# board.net
KiCad netlist of a schematic drawn in EAGLE
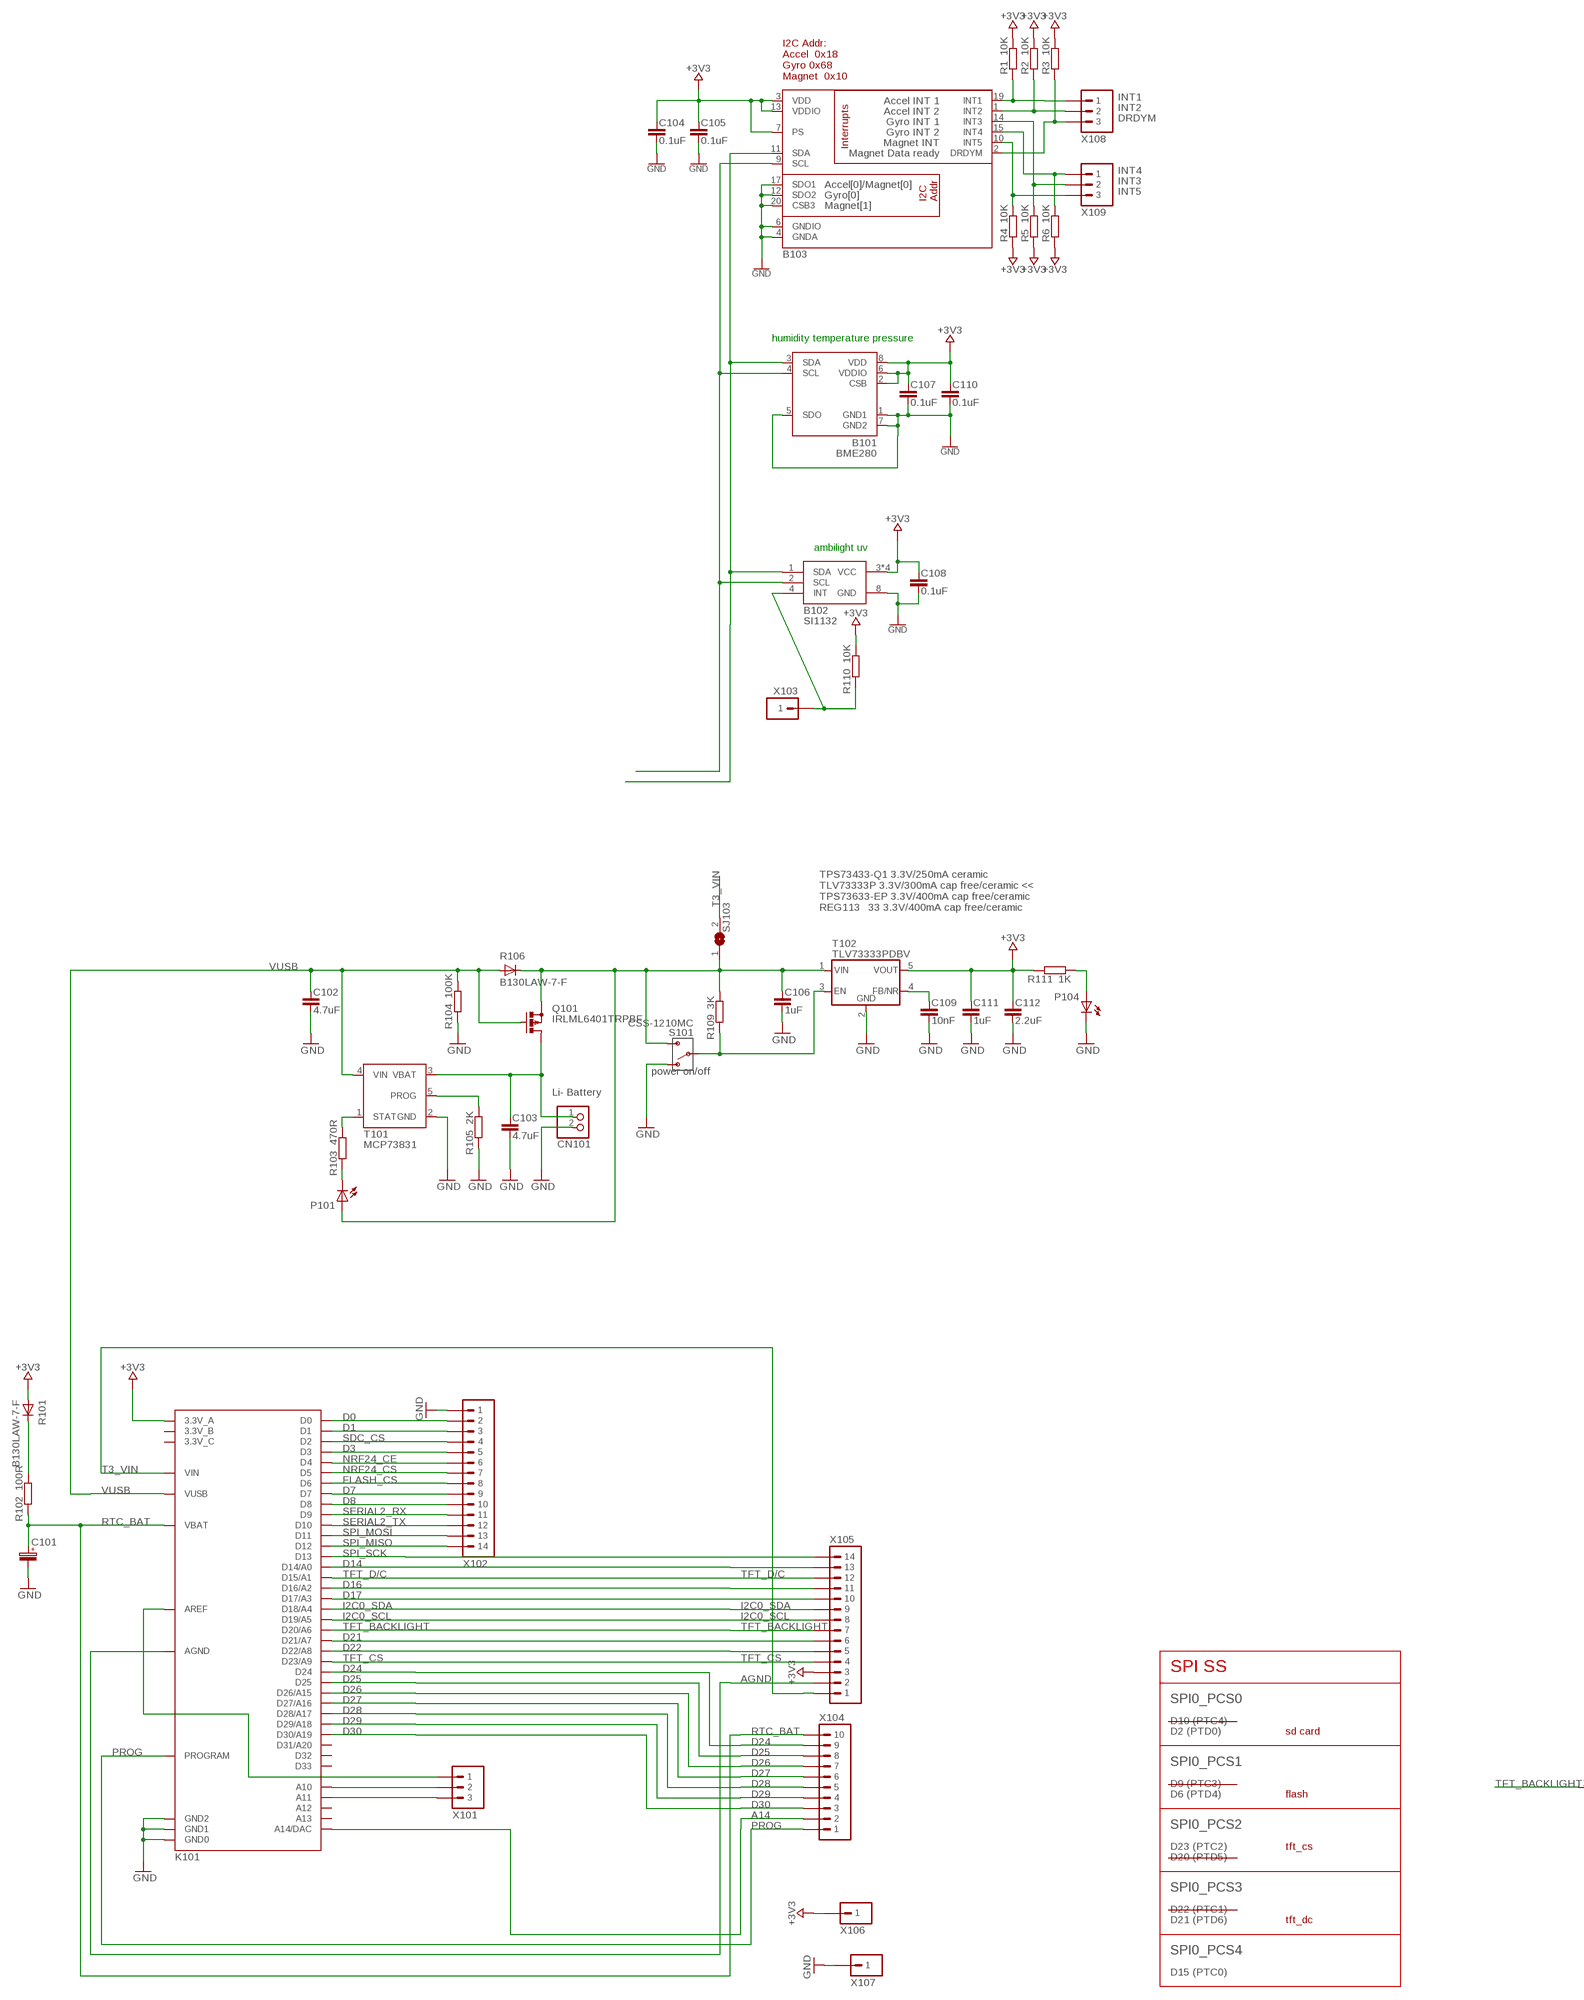
[diagram p0: schematic, sheet 1, part 1 of 2]
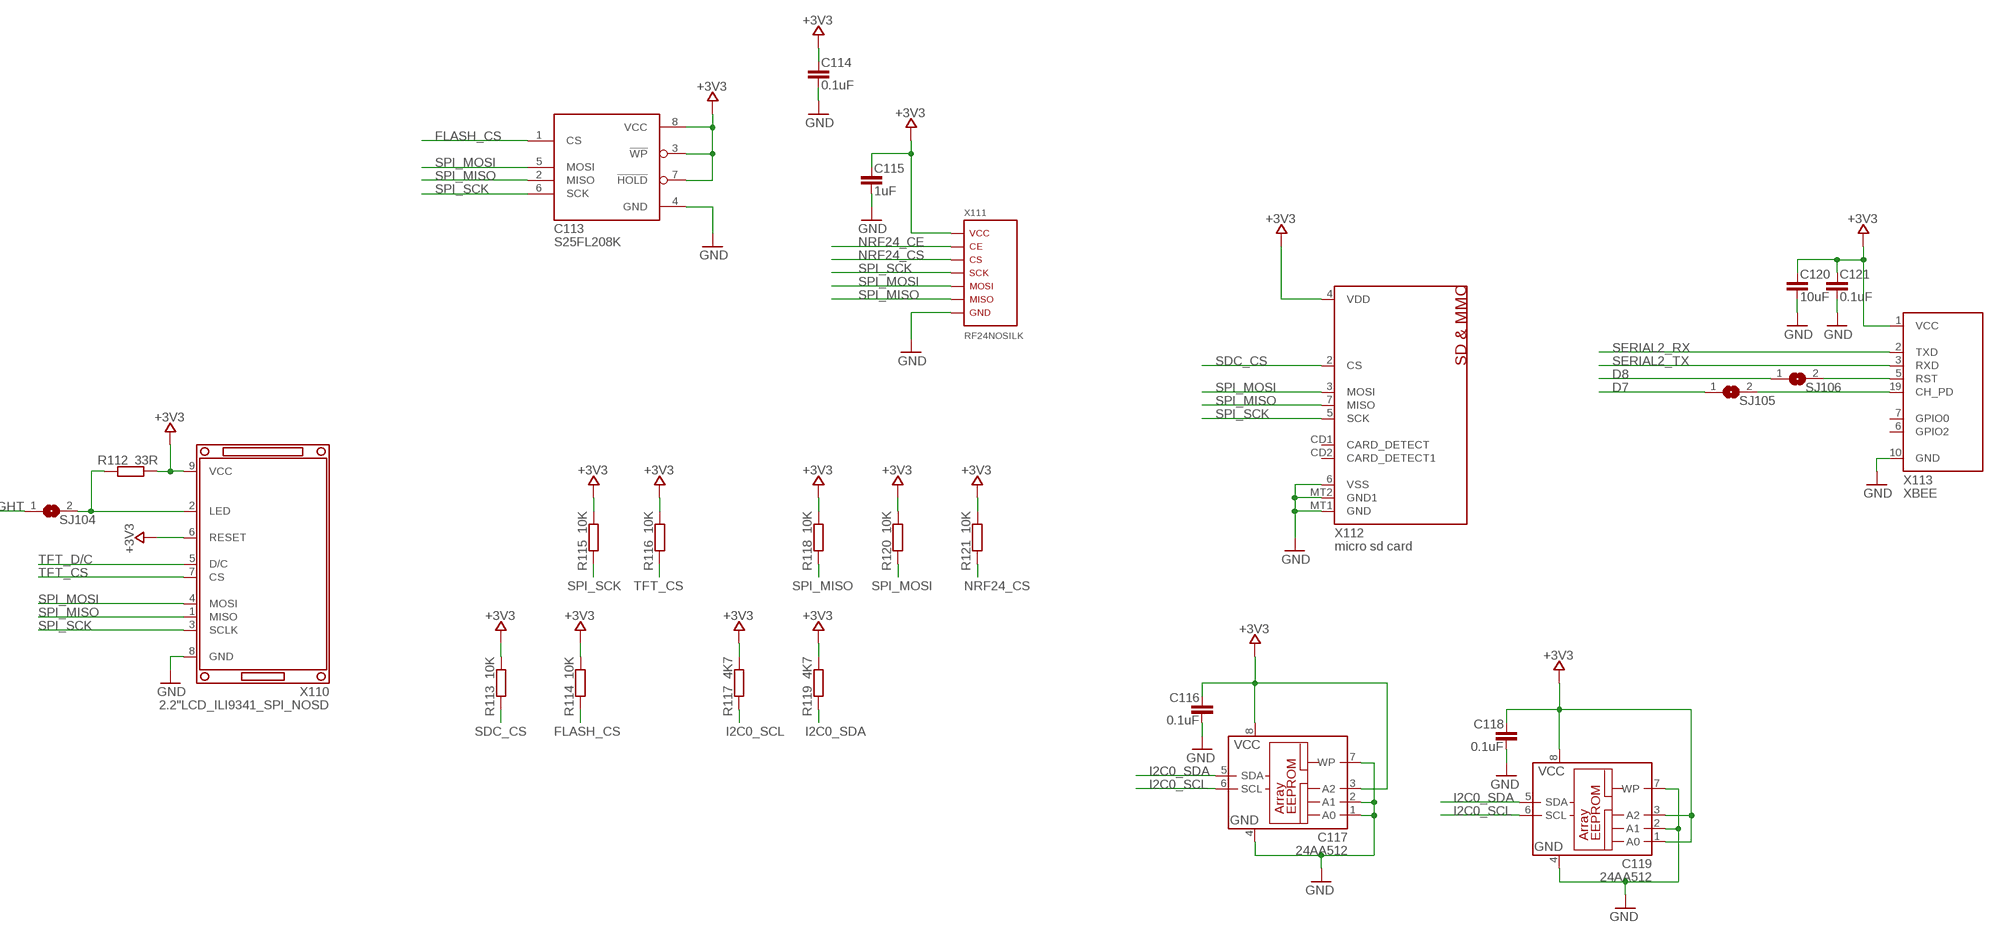
[diagram p1: schematic, sheet 1, part 2 of 2]

(export (version "E")
  (design (tool "Eeschema 10.0.6"))
  (components
    (comp (ref "B101")
      (value "BME280")
      (footprint "eagle-import:BOSCH_8LGA_0.35X0.35")
      (libsource (lib "eagle-import") (part "BME280_I2CLGA8"))
    )
    (comp (ref "B102")
      (value "SI1132")
      (footprint "eagle-import:SILABS_QFN-10_(ONLY_8PAD)")
      (libsource (lib "eagle-import") (part "SI1132QFN10"))
    )
    (comp (ref "B103")
      (value "BMX055")
      (footprint "eagle-import:BMX055_LGA20")
      (libsource (lib "eagle-import") (part "BMX055"))
    )
    (comp (ref "C101")
      (value "CAPACITOR_POLCPH3225A")
      (footprint "eagle-import:CPH3225A")
      (libsource (lib "eagle-import") (part "CAPACITOR_POLCPH3225A"))
    )
    (comp (ref "C102")
      (value "4.7uF")
      (footprint "eagle-import:SMT_M2012(0805)_G1")
      (fields (field (name "MF") "AVX") (field (name "MPN") "0805ZD475KAT2A"))
      (libsource (lib "eagle-import") (part "CAPACITORM2012(0805)_G1"))
    )
    (comp (ref "C103")
      (value "4.7uF")
      (footprint "eagle-import:SMT_M2012(0805)_G1")
      (fields (field (name "MF") "AVX") (field (name "MPN") "0805ZD475KAT2A"))
      (libsource (lib "eagle-import") (part "CAPACITORM2012(0805)_G1"))
    )
    (comp (ref "C104")
      (value "0.1uF")
      (footprint "eagle-import:SMT_M1608(0603)_G1")
      (fields (field (name "MF") "AVX") (field (name "MPN") "0603YC104K4Z2A"))
      (libsource (lib "eagle-import") (part "CAPACITORM1608(0603)_G1"))
    )
    (comp (ref "C105")
      (value "0.1uF")
      (footprint "eagle-import:SMT_M1608(0603)_G1")
      (fields (field (name "MF") "AVX") (field (name "MPN") "0603YC104K4Z2A"))
      (libsource (lib "eagle-import") (part "CAPACITORM1608(0603)_G1"))
    )
    (comp (ref "C106")
      (value "1uF")
      (footprint "eagle-import:SMT_M1608(0603)_G1")
      (fields (field (name "MF") "AVX") (field (name "MPN") "0603ZD105KAT2A"))
      (libsource (lib "eagle-import") (part "CAPACITORM1608(0603)_G1"))
    )
    (comp (ref "C107")
      (value "0.1uF")
      (footprint "eagle-import:SMT_M1608(0603)_G1")
      (fields (field (name "MF") "AVX") (field (name "MPN") "0603YC104K4Z2A"))
      (libsource (lib "eagle-import") (part "CAPACITORM1608(0603)_G1"))
    )
    (comp (ref "C108")
      (value "0.1uF")
      (footprint "eagle-import:SMT_M1608(0603)_G1")
      (fields (field (name "MF") "AVX") (field (name "MPN") "0603YC104K4Z2A"))
      (libsource (lib "eagle-import") (part "CAPACITORM1608(0603)_G1"))
    )
    (comp (ref "C109")
      (value "10nF")
      (footprint "eagle-import:SMT_M1608(0603)_G1")
      (fields (field (name "MF") "MULTICOMP") (field (name "MPN") "MC0603B103K500CT"))
      (libsource (lib "eagle-import") (part "CAPACITORM1608(0603)_G1"))
    )
    (comp (ref "C110")
      (value "0.1uF")
      (footprint "eagle-import:SMT_M1608(0603)_G1")
      (fields (field (name "MF") "AVX") (field (name "MPN") "0603YC104K4Z2A"))
      (libsource (lib "eagle-import") (part "CAPACITORM1608(0603)_G1"))
    )
    (comp (ref "C111")
      (value "1uF")
      (footprint "eagle-import:SMT_M1608(0603)_G1")
      (fields (field (name "MF") "AVX") (field (name "MPN") "0603ZD105KAT2A"))
      (libsource (lib "eagle-import") (part "CAPACITORM1608(0603)_G1"))
    )
    (comp (ref "C112")
      (value "2.2uF")
      (footprint "eagle-import:SMT_M2012(0805)_G1")
      (fields (field (name "MF") "KEMET") (field (name "MPN") "C1206C226K9PACTU"))
      (libsource (lib "eagle-import") (part "CAPACITORM2012(0805)_G1"))
    )
    (comp (ref "C113")
      (value "S25FL208K")
      (footprint "eagle-import:SOIC-8")
      (fields (field (name "MF") "SPANSION") (field (name "MPN") "S25FL208K0RMFI041"))
      (libsource (lib "eagle-import") (part "SPI_FLASH-X25XXSOIC_150MIL_2"))
    )
    (comp (ref "C114")
      (value "0.1uF")
      (footprint "eagle-import:SMT_M1608(0603)_G1")
      (fields (field (name "MF") "AVX") (field (name "MPN") "0603YC104K4Z2A"))
      (libsource (lib "eagle-import") (part "CAPACITORM1608(0603)_G1"))
    )
    (comp (ref "C115")
      (value "1uF")
      (footprint "eagle-import:SMT_M1608(0603)_G1")
      (fields (field (name "MF") "AVX") (field (name "MPN") "0603ZD105KAT2A"))
      (libsource (lib "eagle-import") (part "CAPACITORM1608(0603)_G1"))
    )
    (comp (ref "C116")
      (value "0.1uF")
      (footprint "eagle-import:SMT_M1608(0603)_G1")
      (fields (field (name "MF") "AVX") (field (name "MPN") "0603YC104K4Z2A"))
      (libsource (lib "eagle-import") (part "CAPACITORM1608(0603)_G1"))
    )
    (comp (ref "C117")
      (value "24AA512")
      (footprint "eagle-import:SOIC-8")
      (fields (field (name "MF") "MICROCHIP") (field (name "MPN") "24AA512-I/SM"))
      (libsource (lib "eagle-import") (part "EEPROM24AAXXXSN"))
    )
    (comp (ref "C118")
      (value "0.1uF")
      (footprint "eagle-import:SMT_M1608(0603)_G1")
      (fields (field (name "MF") "AVX") (field (name "MPN") "0603YC104K4Z2A"))
      (libsource (lib "eagle-import") (part "CAPACITORM1608(0603)_G1"))
    )
    (comp (ref "C119")
      (value "24AA512")
      (footprint "eagle-import:SOIC-8")
      (fields (field (name "MF") "MICROCHIP") (field (name "MPN") "24AA512-I/SM"))
      (libsource (lib "eagle-import") (part "EEPROM24AAXXXSN"))
    )
    (comp (ref "C120")
      (value "10uF")
      (footprint "eagle-import:SMT_M2012(0805)_G1")
      (fields (field (name "MF") "MULTICOMP") (field (name "MPN") "MCTT31F106Z100CT"))
      (libsource (lib "eagle-import") (part "CAPACITORM2012(0805)_G1"))
    )
    (comp (ref "C121")
      (value "0.1uF")
      (footprint "eagle-import:SMT_M1608(0603)_G1")
      (fields (field (name "MF") "AVX") (field (name "MPN") "0603YC104K4Z2A"))
      (libsource (lib "eagle-import") (part "CAPACITORM1608(0603)_G1"))
    )
    (comp (ref "CN101")
      (value "JST_2PIN-SMT-RA")
      (footprint "eagle-import:JST-PH-2-SMT-RA")
      (fields
        (field (name "MF") "JST (JAPAN SOLDERLESS TERMINALS)")
        (field (name "MPN") "S2B-PH-SM4-TB(LF)(SN)")
      )
      (libsource (lib "eagle-import") (part "JST_2PIN-SMT-RA"))
    )
    (comp (ref "K101")
      (value "TEENSY3.1_ALLPINSNOSILK")
      (footprint "eagle-import:TEENSY3.1_ALLPINS_NOSILK")
      (libsource (lib "eagle-import") (part "TEENSY3.1_ALLPINSNOSILK"))
    )
    (comp (ref "P101")
      (value "LEDSMT_M1608(0603)_LED_G1")
      (footprint "eagle-import:SMT_M1608(0603)_LED_G1")
      (fields (field (name "MF") "VISHAY SEMICONDUCTOR") (field (name "MPN") "TLMS1100-GS08"))
      (libsource (lib "eagle-import") (part "LEDSMT_M1608(0603)_LED_G1"))
    )
    (comp (ref "P104")
      (value "LEDSMT_M1608(0603)_LED_G1")
      (footprint "eagle-import:SMT_M1608(0603)_LED_G1")
      (fields (field (name "MF") "VISHAY SEMICONDUCTOR") (field (name "MPN") "TLMS1100-GS08"))
      (libsource (lib "eagle-import") (part "LEDSMT_M1608(0603)_LED_G1"))
    )
    (comp (ref "Q101")
      (value "IRLML6401TRPBF")
      (footprint "eagle-import:SOT23-SPEC1")
      (fields (field (name "MF") "INTERNATIONAL RECTIFIER"))
      (libsource (lib "eagle-import") (part "PFETSOT-23_SPEC1"))
    )
    (comp (ref "R1")
      (value "10K")
      (footprint "eagle-import:SMT_M1608(0603)_G1")
      (fields (field (name "MF") "VISHAY DRALORIC") (field (name "MPN") "CRCW060310K0FKEA"))
      (libsource (lib "eagle-import") (part "RESISTORM1608(0603)_G1"))
    )
    (comp (ref "R2")
      (value "10K")
      (footprint "eagle-import:SMT_M1608(0603)_G1")
      (fields (field (name "MF") "VISHAY DRALORIC") (field (name "MPN") "CRCW060310K0FKEA"))
      (libsource (lib "eagle-import") (part "RESISTORM1608(0603)_G1"))
    )
    (comp (ref "R3")
      (value "10K")
      (footprint "eagle-import:SMT_M1608(0603)_G1")
      (fields (field (name "MF") "VISHAY DRALORIC") (field (name "MPN") "CRCW060310K0FKEA"))
      (libsource (lib "eagle-import") (part "RESISTORM1608(0603)_G1"))
    )
    (comp (ref "R4")
      (value "10K")
      (footprint "eagle-import:SMT_M1608(0603)_G1")
      (fields (field (name "MF") "VISHAY DRALORIC") (field (name "MPN") "CRCW060310K0FKEA"))
      (libsource (lib "eagle-import") (part "RESISTORM1608(0603)_G1"))
    )
    (comp (ref "R5")
      (value "10K")
      (footprint "eagle-import:SMT_M1608(0603)_G1")
      (fields (field (name "MF") "VISHAY DRALORIC") (field (name "MPN") "CRCW060310K0FKEA"))
      (libsource (lib "eagle-import") (part "RESISTORM1608(0603)_G1"))
    )
    (comp (ref "R6")
      (value "10K")
      (footprint "eagle-import:SMT_M1608(0603)_G1")
      (fields (field (name "MF") "VISHAY DRALORIC") (field (name "MPN") "CRCW060310K0FKEA"))
      (libsource (lib "eagle-import") (part "RESISTORM1608(0603)_G1"))
    )
    (comp (ref "R101")
      (value "B130LAW-7-F")
      (footprint "eagle-import:SOD123V2")
      (fields (field (name "MF") "DIODES INC."))
      (libsource (lib "eagle-import") (part "DIODESOD123-V2"))
    )
    (comp (ref "R102")
      (value "100R")
      (footprint "eagle-import:SMT_M1608(0603)_G1")
      (fields (field (name "MF") "VISHAY DRALORIC") (field (name "MPN") "CRCW060310K0FKEA"))
      (libsource (lib "eagle-import") (part "RESISTORM1608(0603)_G1"))
    )
    (comp (ref "R103")
      (value "470R")
      (footprint "eagle-import:SMT_M1608(0603)_G1")
      (fields (field (name "MF") "VISHAY DRALORIC") (field (name "MPN") "CRCW0603470RFKEA"))
      (libsource (lib "eagle-import") (part "RESISTORM1608(0603)_G1"))
    )
    (comp (ref "R104")
      (value "100K")
      (footprint "eagle-import:SMT_M1608(0603)_G1")
      (fields (field (name "MF") "VISHAY DRALORIC") (field (name "MPN") "CRCW060310K0FKEA"))
      (libsource (lib "eagle-import") (part "RESISTORM1608(0603)_G1"))
    )
    (comp (ref "R105")
      (value "2K")
      (footprint "eagle-import:SMT_M1608(0603)_G1")
      (fields (field (name "MF") "VISHAY DRALORIC") (field (name "MPN") "CRCW06032K00FKEA"))
      (libsource (lib "eagle-import") (part "RESISTORM1608(0603)_G1"))
    )
    (comp (ref "R106")
      (value "B130LAW-7-F")
      (footprint "eagle-import:SOD123V2")
      (fields (field (name "MF") "DIODES INC."))
      (libsource (lib "eagle-import") (part "DIODESOD123-V2"))
    )
    (comp (ref "R109")
      (value "3K")
      (footprint "eagle-import:SMT_M1608(0603)_G1")
      (fields (field (name "MF") "VISHAY DRALORIC") (field (name "MPN") "CRCW06033K00FKEA"))
      (libsource (lib "eagle-import") (part "RESISTORM1608(0603)_G1"))
    )
    (comp (ref "R110")
      (value "10K")
      (footprint "eagle-import:SMT_M1608(0603)_G1")
      (libsource (lib "eagle-import") (part "RESISTORM1608(0603)_G1"))
    )
    (comp (ref "R111")
      (value "1K")
      (footprint "eagle-import:SMT_M1608(0603)_G1")
      (fields (field (name "MF") "VISHAY DRALORIC") (field (name "MPN") "CRCW0603330RFKEA"))
      (libsource (lib "eagle-import") (part "RESISTORM1608(0603)_G1"))
    )
    (comp (ref "R112")
      (value "33R")
      (footprint "eagle-import:SMT_M1608(0603)_G1")
      (fields (field (name "MF") "VISHAY DRALORIC") (field (name "MPN") "CRCW0805100RFKEA"))
      (libsource (lib "eagle-import") (part "RESISTORM1608(0603)_G1"))
    )
    (comp (ref "R113")
      (value "10K")
      (footprint "eagle-import:SMT_M1608(0603)_G1")
      (fields (field (name "MF") "VISHAY DRALORIC") (field (name "MPN") "CRCW060310K0FKEA"))
      (libsource (lib "eagle-import") (part "RESISTORM1608(0603)_G1"))
    )
    (comp (ref "R114")
      (value "10K")
      (footprint "eagle-import:SMT_M1608(0603)_G1")
      (fields (field (name "MF") "VISHAY DRALORIC") (field (name "MPN") "CRCW060310K0FKEA"))
      (libsource (lib "eagle-import") (part "RESISTORM1608(0603)_G1"))
    )
    (comp (ref "R115")
      (value "10K")
      (footprint "eagle-import:SMT_M1608(0603)_G1")
      (fields (field (name "MF") "VISHAY DRALORIC") (field (name "MPN") "CRCW060310K0FKEA"))
      (libsource (lib "eagle-import") (part "RESISTORM1608(0603)_G1"))
    )
    (comp (ref "R116")
      (value "10K")
      (footprint "eagle-import:SMT_M1608(0603)_G1")
      (fields (field (name "MF") "VISHAY DRALORIC") (field (name "MPN") "CRCW060310K0FKEA"))
      (libsource (lib "eagle-import") (part "RESISTORM1608(0603)_G1"))
    )
    (comp (ref "R117")
      (value "4K7")
      (footprint "eagle-import:SMT_M1608(0603)_G1")
      (fields (field (name "MF") "VISHAY DRALORIC") (field (name "MPN") "CRCW06034K70FKEA"))
      (libsource (lib "eagle-import") (part "RESISTORM1608(0603)_G1"))
    )
    (comp (ref "R118")
      (value "10K")
      (footprint "eagle-import:SMT_M1608(0603)_G1")
      (fields (field (name "MF") "VISHAY DRALORIC") (field (name "MPN") "CRCW060310K0FKEA"))
      (libsource (lib "eagle-import") (part "RESISTORM1608(0603)_G1"))
    )
    (comp (ref "R119")
      (value "4K7")
      (footprint "eagle-import:SMT_M1608(0603)_G1")
      (fields (field (name "MF") "VISHAY DRALORIC") (field (name "MPN") "CRCW06034K70FKEA"))
      (libsource (lib "eagle-import") (part "RESISTORM1608(0603)_G1"))
    )
    (comp (ref "R120")
      (value "10K")
      (footprint "eagle-import:SMT_M1608(0603)_G1")
      (fields (field (name "MF") "VISHAY DRALORIC") (field (name "MPN") "CRCW060310K0FKEA"))
      (libsource (lib "eagle-import") (part "RESISTORM1608(0603)_G1"))
    )
    (comp (ref "R121")
      (value "10K")
      (footprint "eagle-import:SMT_M1608(0603)_G1")
      (fields (field (name "MF") "VISHAY DRALORIC") (field (name "MPN") "CRCW060310K0FKEA"))
      (libsource (lib "eagle-import") (part "RESISTORM1608(0603)_G1"))
    )
    (comp (ref "S101")
      (value "CSS-1210MC")
      (footprint "eagle-import:CSS-1210(M)C")
      (libsource (lib "eagle-import") (part "SLIDE_SWITCH_2WAYCSS-1210(M)C"))
    )
    (comp (ref "SJ103")
      (value "n/a")
      (footprint "eagle-import:SMT_M1608(0603)_G1")
      (libsource (lib "eagle-import") (part "JUMPER_2WRESISTOR0603"))
    )
    (comp (ref "SJ104")
      (value "n/a")
      (footprint "eagle-import:SMT_M1608(0603)_G1")
      (libsource (lib "eagle-import") (part "JUMPER_2WRESISTOR0603"))
    )
    (comp (ref "SJ105")
      (value "0R")
      (footprint "eagle-import:SMT_M1608(0603)_G1")
      (libsource (lib "eagle-import") (part "JUMPER_2WRESISTOR0603"))
    )
    (comp (ref "SJ106")
      (value "0R")
      (footprint "eagle-import:SMT_M1608(0603)_G1")
      (libsource (lib "eagle-import") (part "JUMPER_2WRESISTOR0603"))
    )
    (comp (ref "T101")
      (value "MCP73831")
      (footprint "eagle-import:SOT23-5_MICROCHIP")
      (fields (field (name "MF") "MICROCHIP") (field (name "MPN") "MCP73831T-2ATI/OT"))
      (libsource (lib "eagle-import") (part "MCP73831XXXX/OT_(SOT-23)"))
    )
    (comp (ref "T102")
      (value "TLV73333PDBV")
      (footprint "eagle-import:R-PDSO-G5")
      (fields (field (name "MF") "TEXAS INSTRUMENTS") (field (name "MPN") "TLV73333PDBVT"))
      (libsource (lib "eagle-import") (part "TPS736XXDBV_1"))
    )
    (comp (ref "X101")
      (value "3P1/MIN_SILK2")
      (footprint "eagle-import:HEADER_1X3_1_MIN_SILK2")
      (libsource (lib "eagle-import") (part "3P1/MIN_SILK2"))
    )
    (comp (ref "X102")
      (value "14P1/MIN_SILK2")
      (footprint "eagle-import:HEADER_1X14_1_MIN_SILK2")
      (libsource (lib "eagle-import") (part "14P1/MIN_SILK2"))
    )
    (comp (ref "X103")
      (value "1P1/MIN_SILK2")
      (footprint "eagle-import:HEADER_1X1_1_MIN_SILK2")
      (libsource (lib "eagle-import") (part "1P1/MIN_SILK2"))
    )
    (comp (ref "X104")
      (value "10P1X10P_1/MIN_SILK2")
      (footprint "eagle-import:HEADER_1X10_1_MIN_SILK2")
      (libsource (lib "eagle-import") (part "10P1X10P_1/MIN_SILK2"))
    )
    (comp (ref "X105")
      (value "14P1/MIN_SILK2")
      (footprint "eagle-import:HEADER_1X14_1_MIN_SILK2")
      (libsource (lib "eagle-import") (part "14P1/MIN_SILK2"))
    )
    (comp (ref "X106")
      (value "1P1/MIN_SILK2")
      (footprint "eagle-import:HEADER_1X1_1_MIN_SILK2")
      (libsource (lib "eagle-import") (part "1P1/MIN_SILK2"))
    )
    (comp (ref "X107")
      (value "1P1/MIN_SILK2")
      (footprint "eagle-import:HEADER_1X1_1_MIN_SILK2")
      (libsource (lib "eagle-import") (part "1P1/MIN_SILK2"))
    )
    (comp (ref "X108")
      (value "3P1/MIN_SILK2")
      (footprint "eagle-import:HEADER_1X3_1_MIN_SILK2")
      (libsource (lib "eagle-import") (part "3P1/MIN_SILK2"))
    )
    (comp (ref "X109")
      (value "3P1/MIN_SILK2")
      (footprint "eagle-import:HEADER_1X3_1_MIN_SILK2")
      (libsource (lib "eagle-import") (part "3P1/MIN_SILK2"))
    )
    (comp (ref "X110")
      (value "2.2\"LCD_ILI9341_SPI_NOSD")
      (footprint "eagle-import:2.2_TFT1")
      (libsource (lib "eagle-import") (part "2.2{dblquote}LCD_ILI9341_SPI_NOSD"))
    )
    (comp (ref "X111")
      (value "RF24NOSILK")
      (footprint "eagle-import:RF24_NOSILK")
      (libsource (lib "eagle-import") (part "RF24NOSILK"))
    )
    (comp (ref "X112")
      (value "micro sd card")
      (footprint "eagle-import:MICROSD")
      (fields (field (name "MF") "GLOBAL CONNECTOR TECHNOLOGY") (field (name "MPN") "MEM2051-00-195-00-A."))
      (libsource (lib "eagle-import") (part "MICROSD"))
    )
    (comp (ref "X113")
      (value "XBEE")
      (footprint "eagle-import:ESP_BEE_PTH_VCC_GND_RX_TX_PD_RST_IO0_IO2")
      (libsource (lib "eagle-import") (part "EXP-BEE-SMALLPTH"))
    )
  )
  (nets
    (net (code "1") (name "+3V3") (class "Default")
      (node (ref "B101") (pin "2") (pinfunction "CSB_2") (pintype "bidirectional"))
      (node (ref "B101") (pin "6") (pinfunction "VDDIO_6") (pintype "bidirectional"))
      (node (ref "B101") (pin "8") (pinfunction "VDD_8") (pintype "bidirectional"))
      (node (ref "B102") (pin "3") (pinfunction "VCC_3") (pintype "bidirectional"))
      (node (ref "B102") (pin "6") (pinfunction "VCC_6") (pintype "bidirectional"))
      (node (ref "B102") (pin "7") (pinfunction "VCC_7") (pintype "bidirectional"))
      (node (ref "B102") (pin "9") (pinfunction "VCC_9") (pintype "bidirectional"))
      (node (ref "B103") (pin "13") (pinfunction "VDDIO_13") (pintype "bidirectional"))
      (node (ref "B103") (pin "3") (pinfunction "VDD_3") (pintype "bidirectional"))
      (node (ref "B103") (pin "7") (pinfunction "PS_7") (pintype "bidirectional"))
      (node (ref "C104") (pin "1") (pinfunction "1_1") (pintype "passive"))
      (node (ref "C105") (pin "1") (pinfunction "1_1") (pintype "passive"))
      (node (ref "C107") (pin "1") (pinfunction "1_1") (pintype "passive"))
      (node (ref "C108") (pin "1") (pinfunction "1_1") (pintype "passive"))
      (node (ref "C110") (pin "1") (pinfunction "1_1") (pintype "passive"))
      (node (ref "C111") (pin "1") (pinfunction "1_1") (pintype "passive"))
      (node (ref "C112") (pin "1") (pinfunction "1_1") (pintype "passive"))
      (node (ref "C113") (pin "3") (pinfunction "~{WP}_3") (pintype "bidirectional"))
      (node (ref "C113") (pin "7") (pinfunction "~{HOLD}_7") (pintype "bidirectional"))
      (node (ref "C113") (pin "8") (pinfunction "VCC_8") (pintype "bidirectional"))
      (node (ref "C114") (pin "1") (pinfunction "1_1") (pintype "passive"))
      (node (ref "C115") (pin "1") (pinfunction "1_1") (pintype "passive"))
      (node (ref "C116") (pin "1") (pinfunction "1_1") (pintype "passive"))
      (node (ref "C117") (pin "3") (pinfunction "A2_3") (pintype "input"))
      (node (ref "C117") (pin "8") (pinfunction "VCC_8") (pintype "power_in"))
      (node (ref "C118") (pin "1") (pinfunction "1_1") (pintype "passive"))
      (node (ref "C119") (pin "1") (pinfunction "A0_1") (pintype "input"))
      (node (ref "C119") (pin "3") (pinfunction "A2_3") (pintype "input"))
      (node (ref "C119") (pin "8") (pinfunction "VCC_8") (pintype "power_in"))
      (node (ref "C120") (pin "1") (pinfunction "1_1") (pintype "passive"))
      (node (ref "C121") (pin "1") (pinfunction "1_1") (pintype "passive"))
      (node (ref "K101") (pin "3V3_A") (pinfunction "3.3V_A_3V3_A") (pintype "power_in"))
      (node (ref "R1") (pin "2") (pinfunction "2_2") (pintype "passive"))
      (node (ref "R101") (pin "A") (pinfunction "A_A") (pintype "passive"))
      (node (ref "R110") (pin "2") (pinfunction "2_2") (pintype "passive"))
      (node (ref "R111") (pin "1") (pinfunction "1_1") (pintype "passive"))
      (node (ref "R112") (pin "2") (pinfunction "2_2") (pintype "passive"))
      (node (ref "R113") (pin "2") (pinfunction "2_2") (pintype "passive"))
      (node (ref "R114") (pin "2") (pinfunction "2_2") (pintype "passive"))
      (node (ref "R115") (pin "2") (pinfunction "2_2") (pintype "passive"))
      (node (ref "R116") (pin "2") (pinfunction "2_2") (pintype "passive"))
      (node (ref "R117") (pin "2") (pinfunction "2_2") (pintype "passive"))
      (node (ref "R118") (pin "2") (pinfunction "2_2") (pintype "passive"))
      (node (ref "R119") (pin "2") (pinfunction "2_2") (pintype "passive"))
      (node (ref "R120") (pin "2") (pinfunction "2_2") (pintype "passive"))
      (node (ref "R121") (pin "2") (pinfunction "2_2") (pintype "passive"))
      (node (ref "R2") (pin "2") (pinfunction "2_2") (pintype "passive"))
      (node (ref "R3") (pin "2") (pinfunction "2_2") (pintype "passive"))
      (node (ref "R4") (pin "1") (pinfunction "1_1") (pintype "passive"))
      (node (ref "R5") (pin "1") (pinfunction "1_1") (pintype "passive"))
      (node (ref "R6") (pin "1") (pinfunction "1_1") (pintype "passive"))
      (node (ref "T102") (pin "5") (pinfunction "VOUT_5") (pintype "power_in"))
      (node (ref "X105") (pin "3") (pinfunction "3_3") (pintype "passive"))
      (node (ref "X106") (pin "1") (pinfunction "1_1") (pintype "passive"))
      (node (ref "X110") (pin "6") (pinfunction "RESET_6") (pintype "bidirectional"))
      (node (ref "X110") (pin "9") (pinfunction "VCC_9") (pintype "bidirectional"))
      (node (ref "X111") (pin "VCC") (pinfunction "VCC_VCC") (pintype "power_in"))
      (node (ref "X112") (pin "4") (pinfunction "VDD_4") (pintype "power_in"))
      (node (ref "X113") (pin "1") (pinfunction "VCC_1") (pintype "bidirectional"))
    )
    (net (code "2") (name "/3.3V_B") (class "Default")
      (node (ref "K101") (pin "3V3_B") (pinfunction "3.3V_B_3V3_B") (pintype "power_in"))
    )
    (net (code "3") (name "/3.3V_C") (class "Default")
      (node (ref "K101") (pin "3V3_C") (pinfunction "3.3V_C_3V3_C") (pintype "power_in"))
    )
    (net (code "4") (name "/A14") (class "Default")
      (node (ref "K101") (pin "A14") (pinfunction "A14/DAC_A14") (pintype "input"))
      (node (ref "X104") (pin "2") (pinfunction "2_2") (pintype "passive"))
    )
    (net (code "5") (name "/AGND") (class "Default")
      (node (ref "K101") (pin "AGND") (pinfunction "AGND_AGND") (pintype "bidirectional"))
      (node (ref "X105") (pin "2") (pinfunction "2_2") (pintype "passive"))
    )
    (net (code "6") (name "/D0") (class "Default")
      (node (ref "K101") (pin "D0") (pinfunction "D0_D0") (pintype "bidirectional"))
      (node (ref "X102") (pin "2") (pinfunction "2_2") (pintype "passive"))
    )
    (net (code "7") (name "/D1") (class "Default")
      (node (ref "K101") (pin "D1") (pinfunction "D1_D1") (pintype "bidirectional"))
      (node (ref "X102") (pin "3") (pinfunction "3_3") (pintype "passive"))
    )
    (net (code "8") (name "/D3") (class "Default")
      (node (ref "K101") (pin "D3") (pinfunction "D3_D3") (pintype "bidirectional"))
      (node (ref "X102") (pin "5") (pinfunction "5_5") (pintype "passive"))
    )
    (net (code "9") (name "/D7") (class "Default")
      (node (ref "K101") (pin "D7") (pinfunction "D7_D7") (pintype "bidirectional"))
      (node (ref "SJ105") (pin "1") (pinfunction "1_1") (pintype "passive"))
      (node (ref "X102") (pin "9") (pinfunction "9_9") (pintype "passive"))
    )
    (net (code "10") (name "/D8") (class "Default")
      (node (ref "K101") (pin "D8") (pinfunction "D8_D8") (pintype "bidirectional"))
      (node (ref "SJ106") (pin "1") (pinfunction "1_1") (pintype "passive"))
      (node (ref "X102") (pin "10") (pinfunction "10_10") (pintype "passive"))
    )
    (net (code "11") (name "/D14") (class "Default")
      (node (ref "K101") (pin "A0") (pinfunction "D14/A0_A0") (pintype "bidirectional"))
      (node (ref "X105") (pin "13") (pinfunction "13_13") (pintype "passive"))
    )
    (net (code "12") (name "/D16") (class "Default")
      (node (ref "K101") (pin "A2") (pinfunction "D16/A2_A2") (pintype "bidirectional"))
      (node (ref "X105") (pin "11") (pinfunction "11_11") (pintype "passive"))
    )
    (net (code "13") (name "/D17") (class "Default")
      (node (ref "K101") (pin "A3") (pinfunction "D17/A3_A3") (pintype "bidirectional"))
      (node (ref "X105") (pin "10") (pinfunction "10_10") (pintype "passive"))
    )
    (net (code "14") (name "/D21") (class "Default")
      (node (ref "K101") (pin "A7") (pinfunction "D21/A7_A7") (pintype "bidirectional"))
      (node (ref "X105") (pin "6") (pinfunction "6_6") (pintype "passive"))
    )
    (net (code "15") (name "/D22") (class "Default")
      (node (ref "K101") (pin "A8") (pinfunction "D22/A8_A8") (pintype "bidirectional"))
      (node (ref "X105") (pin "5") (pinfunction "5_5") (pintype "passive"))
    )
    (net (code "16") (name "/D24") (class "Default")
      (node (ref "K101") (pin "D24") (pinfunction "D24_D24") (pintype "bidirectional"))
      (node (ref "X104") (pin "9") (pinfunction "9_9") (pintype "passive"))
    )
    (net (code "17") (name "/D25") (class "Default")
      (node (ref "K101") (pin "D25") (pinfunction "D25_D25") (pintype "bidirectional"))
      (node (ref "X104") (pin "8") (pinfunction "8_8") (pintype "passive"))
    )
    (net (code "18") (name "/D26") (class "Default")
      (node (ref "K101") (pin "D26") (pinfunction "D26/A15_D26") (pintype "bidirectional"))
      (node (ref "X104") (pin "7") (pinfunction "7_7") (pintype "passive"))
    )
    (net (code "19") (name "/D27") (class "Default")
      (node (ref "K101") (pin "D27") (pinfunction "D27/A16_D27") (pintype "bidirectional"))
      (node (ref "X104") (pin "6") (pinfunction "6_6") (pintype "passive"))
    )
    (net (code "20") (name "/D28") (class "Default")
      (node (ref "K101") (pin "D28") (pinfunction "D28/A17_D28") (pintype "bidirectional"))
      (node (ref "X104") (pin "5") (pinfunction "5_5") (pintype "passive"))
    )
    (net (code "21") (name "/D29") (class "Default")
      (node (ref "K101") (pin "D29") (pinfunction "D29/A18_D29") (pintype "bidirectional"))
      (node (ref "X104") (pin "4") (pinfunction "4_4") (pintype "passive"))
    )
    (net (code "22") (name "/D30") (class "Default")
      (node (ref "K101") (pin "D30") (pinfunction "D30/A19_D30") (pintype "bidirectional"))
      (node (ref "X104") (pin "3") (pinfunction "3_3") (pintype "passive"))
    )
    (net (code "23") (name "/DRDYM") (class "Default")
      (node (ref "B103") (pin "2") (pinfunction "DRDYM_2") (pintype "bidirectional"))
      (node (ref "R3") (pin "1") (pinfunction "1_1") (pintype "passive"))
      (node (ref "X108") (pin "3") (pinfunction "3_3") (pintype "passive"))
    )
    (net (code "24") (name "/FLASH_CS") (class "Default")
      (node (ref "C113") (pin "1") (pinfunction "CS_1") (pintype "bidirectional"))
      (node (ref "K101") (pin "D6") (pinfunction "D6_D6") (pintype "bidirectional"))
      (node (ref "R114") (pin "1") (pinfunction "1_1") (pintype "passive"))
      (node (ref "X102") (pin "8") (pinfunction "8_8") (pintype "passive"))
    )
    (net (code "25") (name "/I2C0_SCL") (class "Default")
      (node (ref "B101") (pin "4") (pinfunction "SCL_4") (pintype "bidirectional"))
      (node (ref "B102") (pin "2") (pinfunction "SCL_2") (pintype "bidirectional"))
      (node (ref "B103") (pin "9") (pinfunction "SCL_9") (pintype "bidirectional"))
      (node (ref "C117") (pin "6") (pinfunction "SCL_6") (pintype "input"))
      (node (ref "C119") (pin "6") (pinfunction "SCL_6") (pintype "input"))
      (node (ref "K101") (pin "A5") (pinfunction "D19/A5_A5") (pintype "bidirectional"))
      (node (ref "R117") (pin "1") (pinfunction "1_1") (pintype "passive"))
      (node (ref "X105") (pin "8") (pinfunction "8_8") (pintype "passive"))
    )
    (net (code "26") (name "/I2C0_SDA") (class "Default")
      (node (ref "B101") (pin "3") (pinfunction "SDA_3") (pintype "bidirectional"))
      (node (ref "B102") (pin "1") (pinfunction "SDA_1") (pintype "bidirectional"))
      (node (ref "B103") (pin "11") (pinfunction "SDA_11") (pintype "bidirectional"))
      (node (ref "C117") (pin "5") (pinfunction "SDA_5") (pintype "bidirectional"))
      (node (ref "C119") (pin "5") (pinfunction "SDA_5") (pintype "bidirectional"))
      (node (ref "K101") (pin "A4") (pinfunction "D18/A4_A4") (pintype "bidirectional"))
      (node (ref "R119") (pin "1") (pinfunction "1_1") (pintype "passive"))
      (node (ref "X105") (pin "9") (pinfunction "9_9") (pintype "passive"))
    )
    (net (code "27") (name "/INT1") (class "Default")
      (node (ref "B103") (pin "19") (pinfunction "INT1_19") (pintype "bidirectional"))
      (node (ref "R1") (pin "1") (pinfunction "1_1") (pintype "passive"))
      (node (ref "X108") (pin "1") (pinfunction "1_1") (pintype "passive"))
    )
    (net (code "28") (name "/INT2") (class "Default")
      (node (ref "B103") (pin "1") (pinfunction "INT2_1") (pintype "bidirectional"))
      (node (ref "R2") (pin "1") (pinfunction "1_1") (pintype "passive"))
      (node (ref "X108") (pin "2") (pinfunction "2_2") (pintype "passive"))
    )
    (net (code "29") (name "/INT3") (class "Default")
      (node (ref "B103") (pin "14") (pinfunction "INT3_14") (pintype "bidirectional"))
      (node (ref "R5") (pin "2") (pinfunction "2_2") (pintype "passive"))
      (node (ref "X109") (pin "2") (pinfunction "2_2") (pintype "passive"))
    )
    (net (code "30") (name "/INT4") (class "Default")
      (node (ref "B103") (pin "15") (pinfunction "INT4_15") (pintype "bidirectional"))
      (node (ref "R6") (pin "2") (pinfunction "2_2") (pintype "passive"))
      (node (ref "X109") (pin "1") (pinfunction "1_1") (pintype "passive"))
    )
    (net (code "31") (name "/INT5") (class "Default")
      (node (ref "B103") (pin "10") (pinfunction "INT5_10") (pintype "bidirectional"))
      (node (ref "R4") (pin "2") (pinfunction "2_2") (pintype "passive"))
      (node (ref "X109") (pin "3") (pinfunction "3_3") (pintype "passive"))
    )
    (net (code "32") (name "/NRF24_CE") (class "Default")
      (node (ref "K101") (pin "D4") (pinfunction "D4_D4") (pintype "bidirectional"))
      (node (ref "X102") (pin "6") (pinfunction "6_6") (pintype "passive"))
      (node (ref "X111") (pin "CE") (pinfunction "CE_CE") (pintype "bidirectional"))
    )
    (net (code "33") (name "/NRF24_CS") (class "Default")
      (node (ref "K101") (pin "D5") (pinfunction "D5_D5") (pintype "bidirectional"))
      (node (ref "R121") (pin "1") (pinfunction "1_1") (pintype "passive"))
      (node (ref "X102") (pin "7") (pinfunction "7_7") (pintype "passive"))
      (node (ref "X111") (pin "CS") (pinfunction "CS_CS") (pintype "input"))
    )
    (net (code "34") (name "/PROG") (class "Default")
      (node (ref "K101") (pin "PROG") (pinfunction "PROGRAM_PROG") (pintype "input"))
      (node (ref "X104") (pin "1") (pinfunction "1_1") (pintype "passive"))
    )
    (net (code "35") (name "/RTC_BAT") (class "Default")
      (node (ref "C101") (pin "+") (pinfunction "+_+") (pintype "passive"))
      (node (ref "K101") (pin "VBAT") (pinfunction "VBAT_VBAT") (pintype "power_in"))
      (node (ref "R102") (pin "1") (pinfunction "1_1") (pintype "passive"))
      (node (ref "X104") (pin "10") (pinfunction "10_10") (pintype "passive"))
    )
    (net (code "36") (name "/SDC_CS") (class "Default")
      (node (ref "K101") (pin "D2") (pinfunction "D2_D2") (pintype "bidirectional"))
      (node (ref "R113") (pin "1") (pinfunction "1_1") (pintype "passive"))
      (node (ref "X102") (pin "4") (pinfunction "4_4") (pintype "passive"))
      (node (ref "X112") (pin "2") (pinfunction "CS_2") (pintype "input"))
    )
    (net (code "37") (name "/SERIAL2_RX") (class "Default")
      (node (ref "K101") (pin "D9") (pinfunction "D9_D9") (pintype "bidirectional"))
      (node (ref "X102") (pin "11") (pinfunction "11_11") (pintype "passive"))
      (node (ref "X113") (pin "2") (pinfunction "TXD_2") (pintype "bidirectional"))
    )
    (net (code "38") (name "/SERIAL2_TX") (class "Default")
      (node (ref "K101") (pin "D10") (pinfunction "D10_D10") (pintype "bidirectional"))
      (node (ref "X102") (pin "12") (pinfunction "12_12") (pintype "passive"))
      (node (ref "X113") (pin "3") (pinfunction "RXD_3") (pintype "bidirectional"))
    )
    (net (code "39") (name "/SPI_MISO") (class "Default")
      (node (ref "C113") (pin "2") (pinfunction "MISO_2") (pintype "bidirectional"))
      (node (ref "K101") (pin "D12") (pinfunction "D12_D12") (pintype "bidirectional"))
      (node (ref "R118") (pin "1") (pinfunction "1_1") (pintype "passive"))
      (node (ref "X102") (pin "14") (pinfunction "14_14") (pintype "passive"))
      (node (ref "X110") (pin "1") (pinfunction "MISO_1") (pintype "bidirectional"))
      (node (ref "X111") (pin "MISO") (pinfunction "MISO_MISO") (pintype "output"))
      (node (ref "X112") (pin "7") (pinfunction "MISO_7") (pintype "output"))
    )
    (net (code "40") (name "/SPI_MOSI") (class "Default")
      (node (ref "C113") (pin "5") (pinfunction "MOSI_5") (pintype "bidirectional"))
      (node (ref "K101") (pin "D11") (pinfunction "D11_D11") (pintype "bidirectional"))
      (node (ref "R120") (pin "1") (pinfunction "1_1") (pintype "passive"))
      (node (ref "X102") (pin "13") (pinfunction "13_13") (pintype "passive"))
      (node (ref "X110") (pin "4") (pinfunction "MOSI_4") (pintype "bidirectional"))
      (node (ref "X111") (pin "MOSI") (pinfunction "MOSI_MOSI") (pintype "input"))
      (node (ref "X112") (pin "3") (pinfunction "MOSI_3") (pintype "input"))
    )
    (net (code "41") (name "/SPI_SCK") (class "Default")
      (node (ref "C113") (pin "6") (pinfunction "SCK_6") (pintype "bidirectional"))
      (node (ref "K101") (pin "D13") (pinfunction "D13_D13") (pintype "bidirectional"))
      (node (ref "R115") (pin "1") (pinfunction "1_1") (pintype "passive"))
      (node (ref "X105") (pin "14") (pinfunction "14_14") (pintype "passive"))
      (node (ref "X110") (pin "3") (pinfunction "SCLK_3") (pintype "bidirectional"))
      (node (ref "X111") (pin "SCK") (pinfunction "SCK_SCK") (pintype "input"))
      (node (ref "X112") (pin "5") (pinfunction "SCK_5") (pintype "input"))
    )
    (net (code "42") (name "/T3_VIN") (class "Default")
      (node (ref "K101") (pin "VIN") (pinfunction "VIN_VIN") (pintype "power_in"))
      (node (ref "SJ103") (pin "2") (pinfunction "2_2") (pintype "passive"))
      (node (ref "X105") (pin "1") (pinfunction "1_1") (pintype "passive"))
    )
    (net (code "43") (name "/TFT_BACKLIGHT") (class "Default")
      (node (ref "K101") (pin "A6") (pinfunction "D20/A6_A6") (pintype "bidirectional"))
      (node (ref "SJ104") (pin "1") (pinfunction "1_1") (pintype "passive"))
      (node (ref "X105") (pin "7") (pinfunction "7_7") (pintype "passive"))
    )
    (net (code "44") (name "/TFT_CS") (class "Default")
      (node (ref "K101") (pin "A9") (pinfunction "D23/A9_A9") (pintype "bidirectional"))
      (node (ref "R116") (pin "1") (pinfunction "1_1") (pintype "passive"))
      (node (ref "X105") (pin "4") (pinfunction "4_4") (pintype "passive"))
      (node (ref "X110") (pin "7") (pinfunction "CS_7") (pintype "bidirectional"))
    )
    (net (code "45") (name "/TFT_D{slash}C") (class "Default")
      (node (ref "K101") (pin "A1") (pinfunction "D15/A1_A1") (pintype "bidirectional"))
      (node (ref "X105") (pin "12") (pinfunction "12_12") (pintype "passive"))
      (node (ref "X110") (pin "5") (pinfunction "D/C_5") (pintype "bidirectional"))
    )
    (net (code "46") (name "/VUSB") (class "Default")
      (node (ref "C102") (pin "1") (pinfunction "1_1") (pintype "passive"))
      (node (ref "K101") (pin "VUSB") (pinfunction "VUSB_VUSB") (pintype "power_in"))
      (node (ref "Q101") (pin "1") (pinfunction "G_1") (pintype "passive"))
      (node (ref "R104") (pin "2") (pinfunction "2_2") (pintype "passive"))
      (node (ref "R106") (pin "A") (pinfunction "A_A") (pintype "passive"))
      (node (ref "T101") (pin "4") (pinfunction "VIN_4") (pintype "bidirectional"))
    )
    (net (code "47") (name "GND") (class "Default")
      (node (ref "B101") (pin "1") (pinfunction "GND1_1") (pintype "bidirectional"))
      (node (ref "B101") (pin "5") (pinfunction "SDO_5") (pintype "bidirectional"))
      (node (ref "B101") (pin "7") (pinfunction "GND2_7") (pintype "bidirectional"))
      (node (ref "B102") (pin "8") (pinfunction "GND_8") (pintype "bidirectional"))
      (node (ref "B103") (pin "12") (pinfunction "SDO2_12") (pintype "bidirectional"))
      (node (ref "B103") (pin "17") (pinfunction "SDO1_17") (pintype "bidirectional"))
      (node (ref "B103") (pin "20") (pinfunction "CSB3_20") (pintype "bidirectional"))
      (node (ref "B103") (pin "4") (pinfunction "GNDA_4") (pintype "bidirectional"))
      (node (ref "B103") (pin "6") (pinfunction "GNDIO_6") (pintype "bidirectional"))
      (node (ref "C101") (pin "-") (pinfunction "-_-") (pintype "passive"))
      (node (ref "C102") (pin "2") (pinfunction "2_2") (pintype "passive"))
      (node (ref "C103") (pin "2") (pinfunction "2_2") (pintype "passive"))
      (node (ref "C104") (pin "2") (pinfunction "2_2") (pintype "passive"))
      (node (ref "C105") (pin "2") (pinfunction "2_2") (pintype "passive"))
      (node (ref "C106") (pin "2") (pinfunction "2_2") (pintype "passive"))
      (node (ref "C107") (pin "2") (pinfunction "2_2") (pintype "passive"))
      (node (ref "C108") (pin "2") (pinfunction "2_2") (pintype "passive"))
      (node (ref "C109") (pin "2") (pinfunction "2_2") (pintype "passive"))
      (node (ref "C110") (pin "2") (pinfunction "2_2") (pintype "passive"))
      (node (ref "C111") (pin "2") (pinfunction "2_2") (pintype "passive"))
      (node (ref "C112") (pin "2") (pinfunction "2_2") (pintype "passive"))
      (node (ref "C113") (pin "4") (pinfunction "GND_4") (pintype "bidirectional"))
      (node (ref "C114") (pin "2") (pinfunction "2_2") (pintype "passive"))
      (node (ref "C115") (pin "2") (pinfunction "2_2") (pintype "passive"))
      (node (ref "C116") (pin "2") (pinfunction "2_2") (pintype "passive"))
      (node (ref "C117") (pin "1") (pinfunction "A0_1") (pintype "input"))
      (node (ref "C117") (pin "2") (pinfunction "A1_2") (pintype "input"))
      (node (ref "C117") (pin "4") (pinfunction "GND_4") (pintype "power_in"))
      (node (ref "C117") (pin "7") (pinfunction "WP_7") (pintype "input"))
      (node (ref "C118") (pin "2") (pinfunction "2_2") (pintype "passive"))
      (node (ref "C119") (pin "2") (pinfunction "A1_2") (pintype "input"))
      (node (ref "C119") (pin "4") (pinfunction "GND_4") (pintype "power_in"))
      (node (ref "C119") (pin "7") (pinfunction "WP_7") (pintype "input"))
      (node (ref "C120") (pin "2") (pinfunction "2_2") (pintype "passive"))
      (node (ref "C121") (pin "2") (pinfunction "2_2") (pintype "passive"))
      (node (ref "CN101") (pin "2") (pinfunction "1_2") (pintype "passive"))
      (node (ref "K101") (pin "GND0") (pinfunction "GND0_GND0") (pintype "power_in"))
      (node (ref "K101") (pin "GND1") (pinfunction "GND1_GND1") (pintype "power_in"))
      (node (ref "K101") (pin "GND2") (pinfunction "GND2_GND2") (pintype "power_in"))
      (node (ref "P104") (pin "C") (pinfunction "C_C") (pintype "passive"))
      (node (ref "R104") (pin "1") (pinfunction "1_1") (pintype "passive"))
      (node (ref "R105") (pin "1") (pinfunction "1_1") (pintype "passive"))
      (node (ref "S101") (pin "1") (pinfunction "O_1") (pintype "passive"))
      (node (ref "T101") (pin "2") (pinfunction "GND_2") (pintype "bidirectional"))
      (node (ref "T102") (pin "2") (pinfunction "GND_2") (pintype "power_in"))
      (node (ref "X102") (pin "1") (pinfunction "1_1") (pintype "passive"))
      (node (ref "X107") (pin "1") (pinfunction "1_1") (pintype "passive"))
      (node (ref "X110") (pin "8") (pinfunction "GND_8") (pintype "bidirectional"))
      (node (ref "X111") (pin "GND") (pinfunction "GND_GND") (pintype "power_in"))
      (node (ref "X112") (pin "6") (pinfunction "VSS_6") (pintype "power_in"))
      (node (ref "X112") (pin "MT1") (pinfunction "GND_MT1") (pintype "power_in"))
      (node (ref "X112") (pin "MT2") (pinfunction "GND1_MT2") (pintype "power_in"))
      (node (ref "X113") (pin "10") (pinfunction "GND_10") (pintype "bidirectional"))
    )
    (net (code "48") (name "Net-(B102-INT)") (class "Default")
      (node (ref "B102") (pin "4") (pinfunction "INT_4") (pintype "bidirectional"))
      (node (ref "R110") (pin "1") (pinfunction "1_1") (pintype "passive"))
      (node (ref "X103") (pin "1") (pinfunction "1_1") (pintype "passive"))
    )
    (net (code "49") (name "Net-(CN101-2)") (class "Default")
      (node (ref "C103") (pin "1") (pinfunction "1_1") (pintype "passive"))
      (node (ref "CN101") (pin "1") (pinfunction "2_1") (pintype "passive"))
      (node (ref "Q101") (pin "3") (pinfunction "D_3") (pintype "passive"))
      (node (ref "T101") (pin "3") (pinfunction "VBAT_3") (pintype "bidirectional"))
    )
    (net (code "50") (name "Net-(K101-PadA10)") (class "Default")
      (node (ref "K101") (pin "A10") (pinfunction "A10_A10") (pintype "bidirectional"))
      (node (ref "X101") (pin "2") (pinfunction "2_2") (pintype "passive"))
    )
    (net (code "51") (name "Net-(K101-PadA11)") (class "Default")
      (node (ref "K101") (pin "A11") (pinfunction "A11_A11") (pintype "bidirectional"))
      (node (ref "X101") (pin "3") (pinfunction "3_3") (pintype "passive"))
    )
    (net (code "52") (name "Net-(K101-PadAREF)") (class "Default")
      (node (ref "K101") (pin "AREF") (pinfunction "AREF_AREF") (pintype "input"))
      (node (ref "X101") (pin "1") (pinfunction "1_1") (pintype "passive"))
    )
    (net (code "53") (name "Net-(P101-PadC)") (class "Default")
      (node (ref "P101") (pin "C") (pinfunction "C_C") (pintype "passive"))
      (node (ref "R103") (pin "1") (pinfunction "1_1") (pintype "passive"))
    )
    (net (code "54") (name "Net-(P104-PadA)") (class "Default")
      (node (ref "P104") (pin "A") (pinfunction "A_A") (pintype "passive"))
      (node (ref "R111") (pin "2") (pinfunction "2_2") (pintype "passive"))
    )
    (net (code "55") (name "Net-(Q101-S)") (class "Default")
      (node (ref "C106") (pin "1") (pinfunction "1_1") (pintype "passive"))
      (node (ref "P101") (pin "A") (pinfunction "A_A") (pintype "passive"))
      (node (ref "Q101") (pin "2") (pinfunction "S_2") (pintype "passive"))
      (node (ref "R106") (pin "K") (pinfunction "C_K") (pintype "passive"))
      (node (ref "R109") (pin "2") (pinfunction "2_2") (pintype "passive"))
      (node (ref "S101") (pin "2") (pinfunction "S_2") (pintype "passive"))
      (node (ref "SJ103") (pin "1") (pinfunction "1_1") (pintype "passive"))
      (node (ref "T102") (pin "1") (pinfunction "VIN_1") (pintype "power_in"))
    )
    (net (code "56") (name "Net-(R101-C)") (class "Default")
      (node (ref "R101") (pin "K") (pinfunction "C_K") (pintype "passive"))
      (node (ref "R102") (pin "2") (pinfunction "2_2") (pintype "passive"))
    )
    (net (code "57") (name "Net-(S101-P)") (class "Default")
      (node (ref "R109") (pin "1") (pinfunction "1_1") (pintype "passive"))
      (node (ref "S101") (pin "3") (pinfunction "P_3") (pintype "passive"))
      (node (ref "T102") (pin "3") (pinfunction "EN_3") (pintype "input"))
    )
    (net (code "58") (name "Net-(T101-PROG)") (class "Default")
      (node (ref "R105") (pin "2") (pinfunction "2_2") (pintype "passive"))
      (node (ref "T101") (pin "5") (pinfunction "PROG_5") (pintype "bidirectional"))
    )
    (net (code "59") (name "Net-(T101-STAT)") (class "Default")
      (node (ref "R103") (pin "2") (pinfunction "2_2") (pintype "passive"))
      (node (ref "T101") (pin "1") (pinfunction "STAT_1") (pintype "bidirectional"))
    )
    (net (code "60") (name "Net-(T102-FB{slash}NR)") (class "Default")
      (node (ref "C109") (pin "1") (pinfunction "1_1") (pintype "passive"))
      (node (ref "T102") (pin "4") (pinfunction "FB/NR_4") (pintype "bidirectional"))
    )
    (net (code "61") (name "Net-(X110-LED)") (class "Default")
      (node (ref "R112") (pin "1") (pinfunction "1_1") (pintype "passive"))
      (node (ref "SJ104") (pin "2") (pinfunction "2_2") (pintype "passive"))
      (node (ref "X110") (pin "2") (pinfunction "LED_2") (pintype "bidirectional"))
    )
    (net (code "62") (name "Net-(X113-CH_PD)") (class "Default")
      (node (ref "SJ105") (pin "2") (pinfunction "2_2") (pintype "passive"))
      (node (ref "X113") (pin "19") (pinfunction "CH_PD_19") (pintype "bidirectional"))
    )
    (net (code "63") (name "Net-(X113-RST)") (class "Default")
      (node (ref "SJ106") (pin "2") (pinfunction "2_2") (pintype "passive"))
      (node (ref "X113") (pin "5") (pinfunction "RST_5") (pintype "bidirectional"))
    )
    (net (code "64") (name "unconnected-(K101-D31{slash}A20-PadD31)") (class "Default")
      (node (ref "K101") (pin "D31") (pinfunction "D31/A20_D31") (pintype "bidirectional"))
    )
    (net (code "65") (name "unconnected-(K101-PadA12)") (class "Default")
      (node (ref "K101") (pin "A12") (pinfunction "A12_A12") (pintype "bidirectional"))
    )
    (net (code "66") (name "unconnected-(K101-PadA13)") (class "Default")
      (node (ref "K101") (pin "A13") (pinfunction "A13_A13") (pintype "bidirectional"))
    )
    (net (code "67") (name "unconnected-(K101-PadD32)") (class "Default")
      (node (ref "K101") (pin "D32") (pinfunction "D32_D32") (pintype "bidirectional"))
    )
    (net (code "68") (name "unconnected-(K101-PadD33)") (class "Default")
      (node (ref "K101") (pin "D33") (pinfunction "D33_D33") (pintype "bidirectional"))
    )
    (net (code "69") (name "unconnected-(X112-CARD_DETECT-PadCD1)") (class "Default")
      (node (ref "X112") (pin "CD1") (pinfunction "CARD_DETECT_CD1") (pintype "passive"))
    )
    (net (code "70") (name "unconnected-(X112-CARD_DETECT1-PadCD2)") (class "Default")
      (node (ref "X112") (pin "CD2") (pinfunction "CARD_DETECT1_CD2") (pintype "passive"))
    )
    (net (code "71") (name "unconnected-(X113-GPIO0-Pad7)") (class "Default")
      (node (ref "X113") (pin "7") (pinfunction "GPIO0_7") (pintype "bidirectional"))
    )
    (net (code "72") (name "unconnected-(X113-GPIO2-Pad6)") (class "Default")
      (node (ref "X113") (pin "6") (pinfunction "GPIO2_6") (pintype "bidirectional"))
    )
  )
)
